# OneBellInterfaceRevC.net
KiCad netlist of a schematic drawn in EAGLE
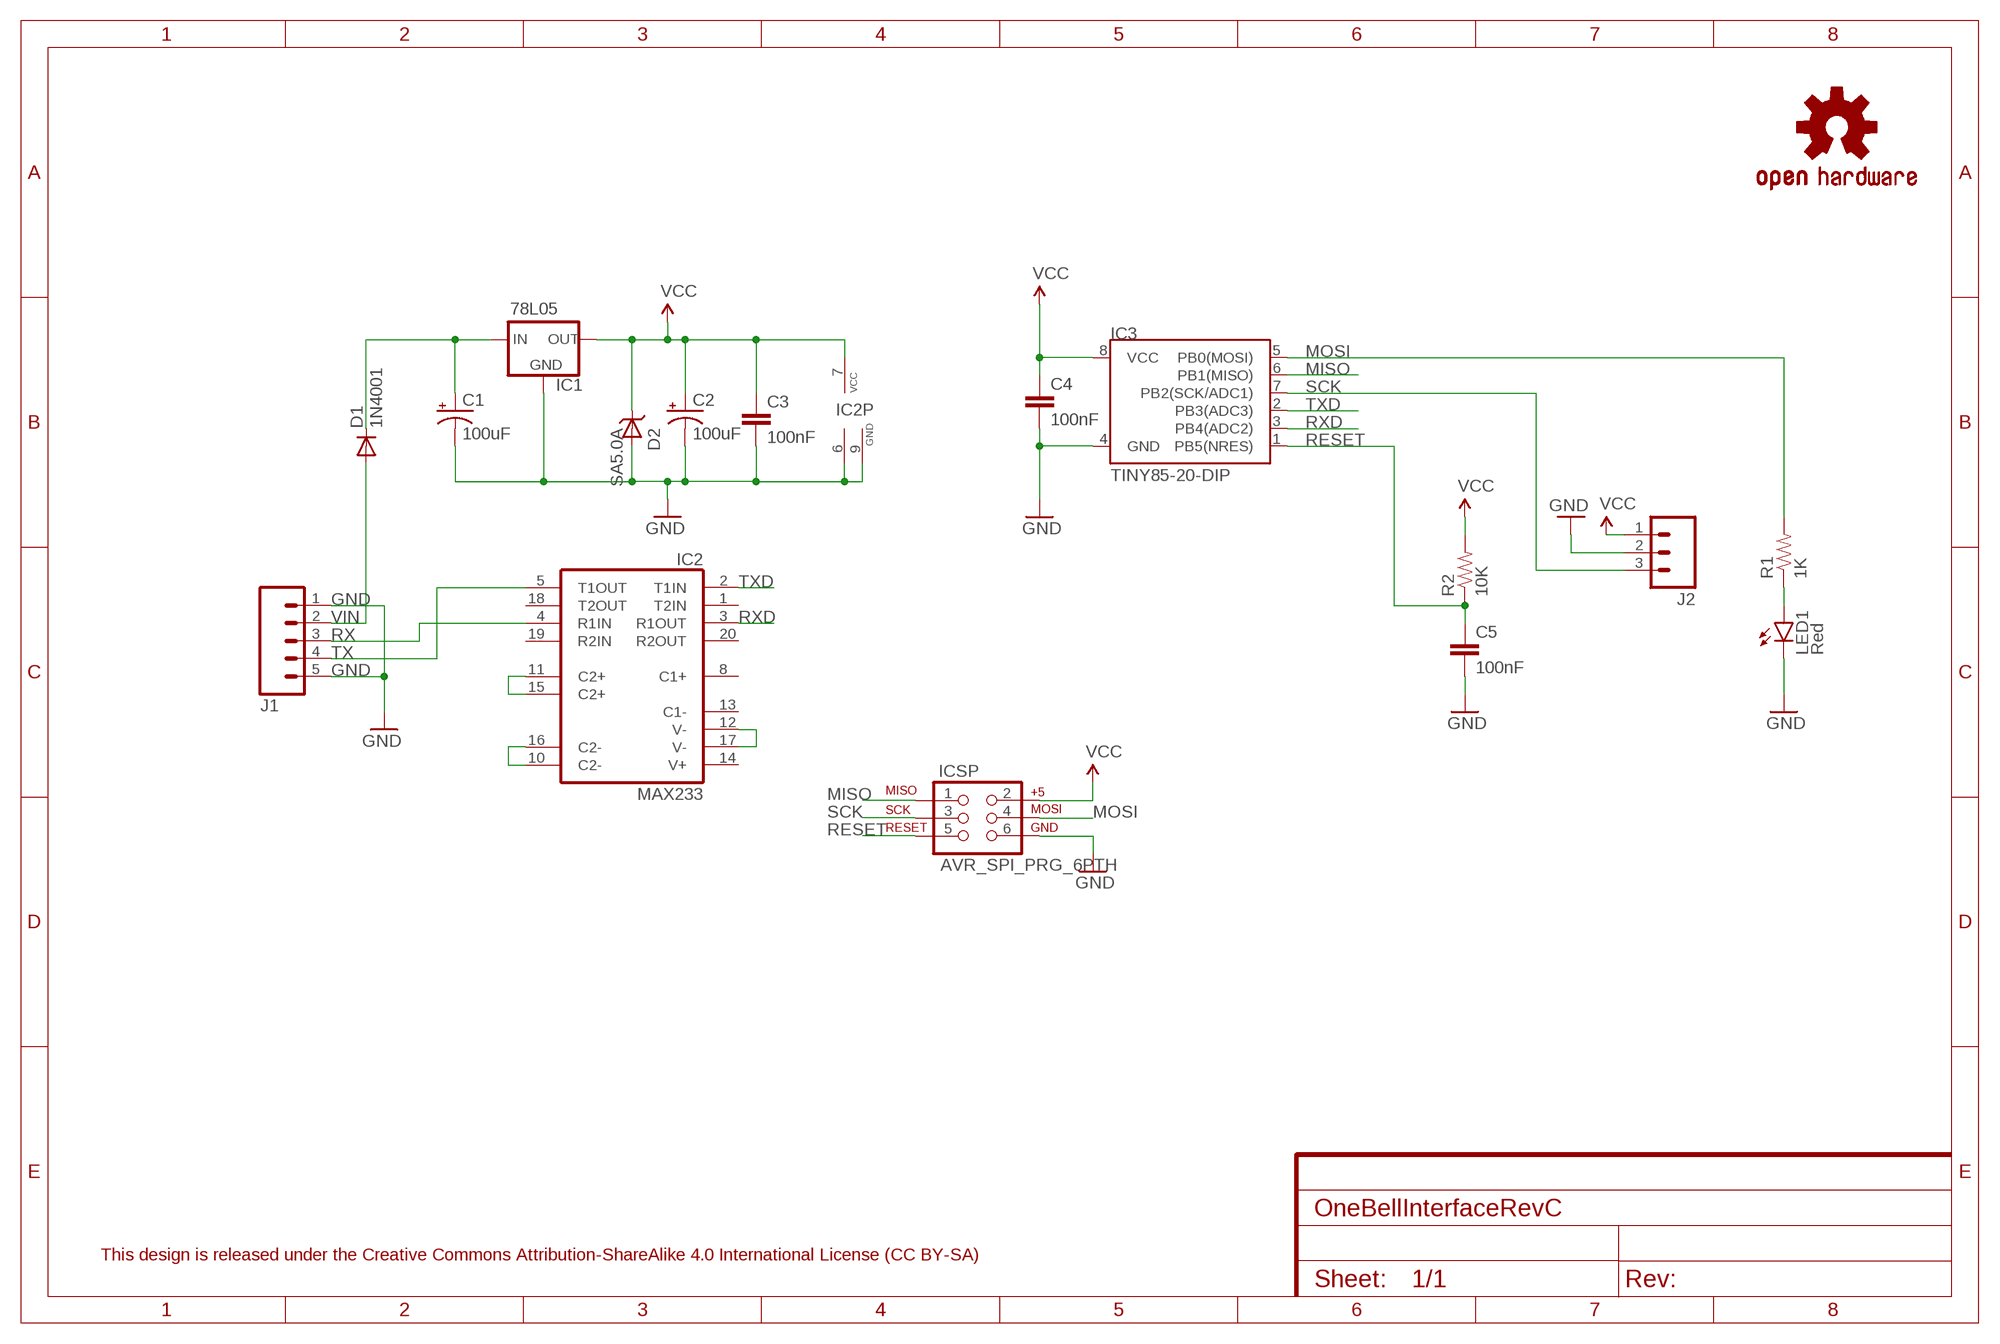
[diagram p0: schematic, sheet 1]

(export (version "E")
  (design (tool "Eeschema 10.0.6"))
  (components
    (comp (ref "C1")
      (value "100uF")
      (footprint "eagle-import:CPOL-RADIAL-100UF-25V")
      (libsource (lib "eagle-import") (part "CAP_POLPTH1"))
    )
    (comp (ref "C2")
      (value "100uF")
      (footprint "eagle-import:CPOL-RADIAL-100UF-25V")
      (libsource (lib "eagle-import") (part "CAP_POLPTH1"))
    )
    (comp (ref "C3")
      (value "100nF")
      (footprint "eagle-import:CAP-PTH-SMALL")
      (libsource (lib "eagle-import") (part "CAPPTH"))
    )
    (comp (ref "C4")
      (value "100nF")
      (footprint "eagle-import:CAP-PTH-SMALL")
      (libsource (lib "eagle-import") (part "CAPPTH"))
    )
    (comp (ref "C5")
      (value "100nF")
      (footprint "eagle-import:CAP-PTH-SMALL")
      (libsource (lib "eagle-import") (part "CAPPTH"))
    )
    (comp (ref "D1")
      (value "1N4001")
      (footprint "eagle-import:DO41_DIODE")
      (libsource (lib "eagle-import") (part "1N4001"))
    )
    (comp (ref "D2")
      (value "SA5.0A")
      (footprint "eagle-import:DO41_TVS_UNI")
      (libsource (lib "eagle-import") (part "SA5.0A"))
    )
    (comp (ref "IC1")
      (value "78L05")
      (footprint "eagle-import:TO-92")
      (libsource (lib "eagle-import") (part "V_REG_78XXTO-92_UNTESTED"))
    )
    (comp (ref "IC2")
      (value "MAX233")
      (footprint "eagle-import:DIL20")
      (fields (field (name "MPN") "MAX233ACPP+G36"))
      (libsource (lib "eagle-import") (part "MAX233"))
    )
    (comp (ref "IC3")
      (value "TINY85-20-DIP")
      (footprint "eagle-import:DIL08")
      (libsource (lib "eagle-import") (part "ATTINY45DIL08_LONG_PADS"))
    )
    (comp (ref "ICSP")
      (value "AVR_SPI_PRG_6PTH")
      (footprint "eagle-import:2X3")
      (libsource (lib "eagle-import") (part "AVR_SPI_PRG_6PTH"))
    )
    (comp (ref "J1")
      (value "M05PTH")
      (footprint "eagle-import:1X05")
      (libsource (lib "eagle-import") (part "M05PTH"))
    )
    (comp (ref "J2")
      (value "M03PTH")
      (footprint "eagle-import:1X03")
      (libsource (lib "eagle-import") (part "M03PTH"))
    )
    (comp (ref "LED1")
      (value "Red")
      (footprint "eagle-import:LED3MM")
      (libsource (lib "eagle-import") (part "LED3MM"))
    )
    (comp (ref "LOGO1")
      (value "OSHW-LOGOS")
      (footprint "eagle-import:OSHW-LOGO-S")
      (libsource (lib "eagle-import") (part "OSHW-LOGOS"))
    )
    (comp (ref "R1")
      (value "1K")
      (footprint "eagle-import:AXIAL-0.4")
      (libsource (lib "eagle-import") (part "RESISTORPTH-1/4W"))
    )
    (comp (ref "R2")
      (value "10K")
      (footprint "eagle-import:AXIAL-0.4")
      (libsource (lib "eagle-import") (part "RESISTORPTH-1/4W"))
    )
  )
  (nets
    (net (code "1") (name "/MISO") (class "Default")
      (node (ref "IC3") (pin "6") (pinfunction "PB1(MISO)_6") (pintype "bidirectional"))
      (node (ref "ICSP") (pin "1") (pinfunction "1_1") (pintype "passive"))
    )
    (net (code "2") (name "/MOSI") (class "Default")
      (node (ref "IC3") (pin "5") (pinfunction "PB0(MOSI)_5") (pintype "bidirectional"))
      (node (ref "ICSP") (pin "4") (pinfunction "4_4") (pintype "passive"))
      (node (ref "R1") (pin "P$2") (pinfunction "2_P$2") (pintype "passive"))
    )
    (net (code "3") (name "/RESET") (class "Default")
      (node (ref "C5") (pin "1") (pinfunction "1_1") (pintype "passive"))
      (node (ref "IC3") (pin "1") (pinfunction "PB5(NRES)_1") (pintype "bidirectional"))
      (node (ref "ICSP") (pin "5") (pinfunction "5_5") (pintype "passive"))
      (node (ref "R2") (pin "P$1") (pinfunction "1_P$1") (pintype "passive"))
    )
    (net (code "4") (name "/RX") (class "Default")
      (node (ref "IC2") (pin "4") (pinfunction "R1IN_4") (pintype "input"))
      (node (ref "J1") (pin "3") (pinfunction "3_3") (pintype "passive"))
    )
    (net (code "5") (name "/RXD") (class "Default")
      (node (ref "IC2") (pin "3") (pinfunction "R1OUT_3") (pintype "output"))
      (node (ref "IC3") (pin "3") (pinfunction "PB4(ADC2)_3") (pintype "bidirectional"))
    )
    (net (code "6") (name "/SCK") (class "Default")
      (node (ref "IC3") (pin "7") (pinfunction "PB2(SCK/ADC1)_7") (pintype "bidirectional"))
      (node (ref "ICSP") (pin "3") (pinfunction "3_3") (pintype "passive"))
      (node (ref "J2") (pin "3") (pinfunction "3_3") (pintype "passive"))
    )
    (net (code "7") (name "/TX") (class "Default")
      (node (ref "IC2") (pin "5") (pinfunction "T1OUT_5") (pintype "output"))
      (node (ref "J1") (pin "4") (pinfunction "4_4") (pintype "passive"))
    )
    (net (code "8") (name "/TXD") (class "Default")
      (node (ref "IC2") (pin "2") (pinfunction "T1IN_2") (pintype "input"))
      (node (ref "IC3") (pin "2") (pinfunction "PB3(ADC3)_2") (pintype "bidirectional"))
    )
    (net (code "9") (name "/VIN") (class "Default")
      (node (ref "D1") (pin "A") (pinfunction "A_A") (pintype "passive"))
      (node (ref "J1") (pin "2") (pinfunction "2_2") (pintype "passive"))
    )
    (net (code "10") (name "GND") (class "Default")
      (node (ref "C1") (pin "2") (pinfunction "-_2") (pintype "passive"))
      (node (ref "C2") (pin "2") (pinfunction "-_2") (pintype "passive"))
      (node (ref "C3") (pin "2") (pinfunction "2_2") (pintype "passive"))
      (node (ref "C4") (pin "2") (pinfunction "2_2") (pintype "passive"))
      (node (ref "C5") (pin "2") (pinfunction "2_2") (pintype "passive"))
      (node (ref "D2") (pin "ANODE") (pinfunction "ANODE_ANODE") (pintype "passive"))
      (node (ref "IC1") (pin "2") (pinfunction "GND_2") (pintype "input"))
      (node (ref "IC2") (pin "6") (pinfunction "GND_6") (pintype "power_in"))
      (node (ref "IC2") (pin "9") (pinfunction "GND_9") (pintype "power_in"))
      (node (ref "IC3") (pin "4") (pinfunction "GND_4") (pintype "bidirectional"))
      (node (ref "ICSP") (pin "6") (pinfunction "6_6") (pintype "passive"))
      (node (ref "J1") (pin "1") (pinfunction "1_1") (pintype "passive"))
      (node (ref "J1") (pin "5") (pinfunction "5_5") (pintype "passive"))
      (node (ref "J2") (pin "2") (pinfunction "2_2") (pintype "passive"))
      (node (ref "LED1") (pin "K") (pinfunction "C_K") (pintype "passive"))
    )
    (net (code "11") (name "Net-(C1-+)") (class "Default")
      (node (ref "C1") (pin "1") (pinfunction "+_1") (pintype "passive"))
      (node (ref "D1") (pin "C") (pinfunction "C_C") (pintype "passive"))
      (node (ref "IC1") (pin "3") (pinfunction "IN_3") (pintype "input"))
    )
    (net (code "12") (name "Net-(IC2A-C2+-Pad11)") (class "Default")
      (node (ref "IC2") (pin "11") (pinfunction "C2+_11") (pintype "bidirectional"))
      (node (ref "IC2") (pin "15") (pinfunction "C2+_15") (pintype "bidirectional"))
    )
    (net (code "13") (name "Net-(IC2A-C2--Pad10)") (class "Default")
      (node (ref "IC2") (pin "10") (pinfunction "C2-_10") (pintype "bidirectional"))
      (node (ref "IC2") (pin "16") (pinfunction "C2-_16") (pintype "bidirectional"))
    )
    (net (code "14") (name "Net-(IC2A-V--Pad12)") (class "Default")
      (node (ref "IC2") (pin "12") (pinfunction "V-_12") (pintype "bidirectional"))
      (node (ref "IC2") (pin "17") (pinfunction "V-_17") (pintype "bidirectional"))
    )
    (net (code "15") (name "Net-(R1-1)") (class "Default")
      (node (ref "LED1") (pin "A") (pinfunction "A_A") (pintype "passive"))
      (node (ref "R1") (pin "P$1") (pinfunction "1_P$1") (pintype "passive"))
    )
    (net (code "16") (name "VCC") (class "Default")
      (node (ref "C2") (pin "1") (pinfunction "+_1") (pintype "passive"))
      (node (ref "C3") (pin "1") (pinfunction "1_1") (pintype "passive"))
      (node (ref "C4") (pin "1") (pinfunction "1_1") (pintype "passive"))
      (node (ref "D2") (pin "CATHODE") (pinfunction "CATHODE_CATHODE") (pintype "passive"))
      (node (ref "IC1") (pin "1") (pinfunction "OUT_1") (pintype "passive"))
      (node (ref "IC2") (pin "7") (pinfunction "VCC_7") (pintype "power_in"))
      (node (ref "IC3") (pin "8") (pinfunction "VCC_8") (pintype "bidirectional"))
      (node (ref "ICSP") (pin "2") (pinfunction "2_2") (pintype "passive"))
      (node (ref "J2") (pin "1") (pinfunction "1_1") (pintype "passive"))
      (node (ref "R2") (pin "P$2") (pinfunction "2_P$2") (pintype "passive"))
    )
    (net (code "17") (name "unconnected-(IC2A-C1+-Pad8)") (class "Default")
      (node (ref "IC2") (pin "8") (pinfunction "C1+_8") (pintype "bidirectional"))
    )
    (net (code "18") (name "unconnected-(IC2A-C1--Pad13)") (class "Default")
      (node (ref "IC2") (pin "13") (pinfunction "C1-_13") (pintype "bidirectional"))
    )
    (net (code "19") (name "unconnected-(IC2A-R2IN-Pad19)") (class "Default")
      (node (ref "IC2") (pin "19") (pinfunction "R2IN_19") (pintype "input"))
    )
    (net (code "20") (name "unconnected-(IC2A-R2OUT-Pad20)") (class "Default")
      (node (ref "IC2") (pin "20") (pinfunction "R2OUT_20") (pintype "output"))
    )
    (net (code "21") (name "unconnected-(IC2A-T2IN-Pad1)") (class "Default")
      (node (ref "IC2") (pin "1") (pinfunction "T2IN_1") (pintype "input"))
    )
    (net (code "22") (name "unconnected-(IC2A-T2OUT-Pad18)") (class "Default")
      (node (ref "IC2") (pin "18") (pinfunction "T2OUT_18") (pintype "output"))
    )
    (net (code "23") (name "unconnected-(IC2A-V+-Pad14)") (class "Default")
      (node (ref "IC2") (pin "14") (pinfunction "V+_14") (pintype "bidirectional"))
    )
  )
)
